# Precharge.net
KiCad netlist of a schematic drawn in Altium Designer
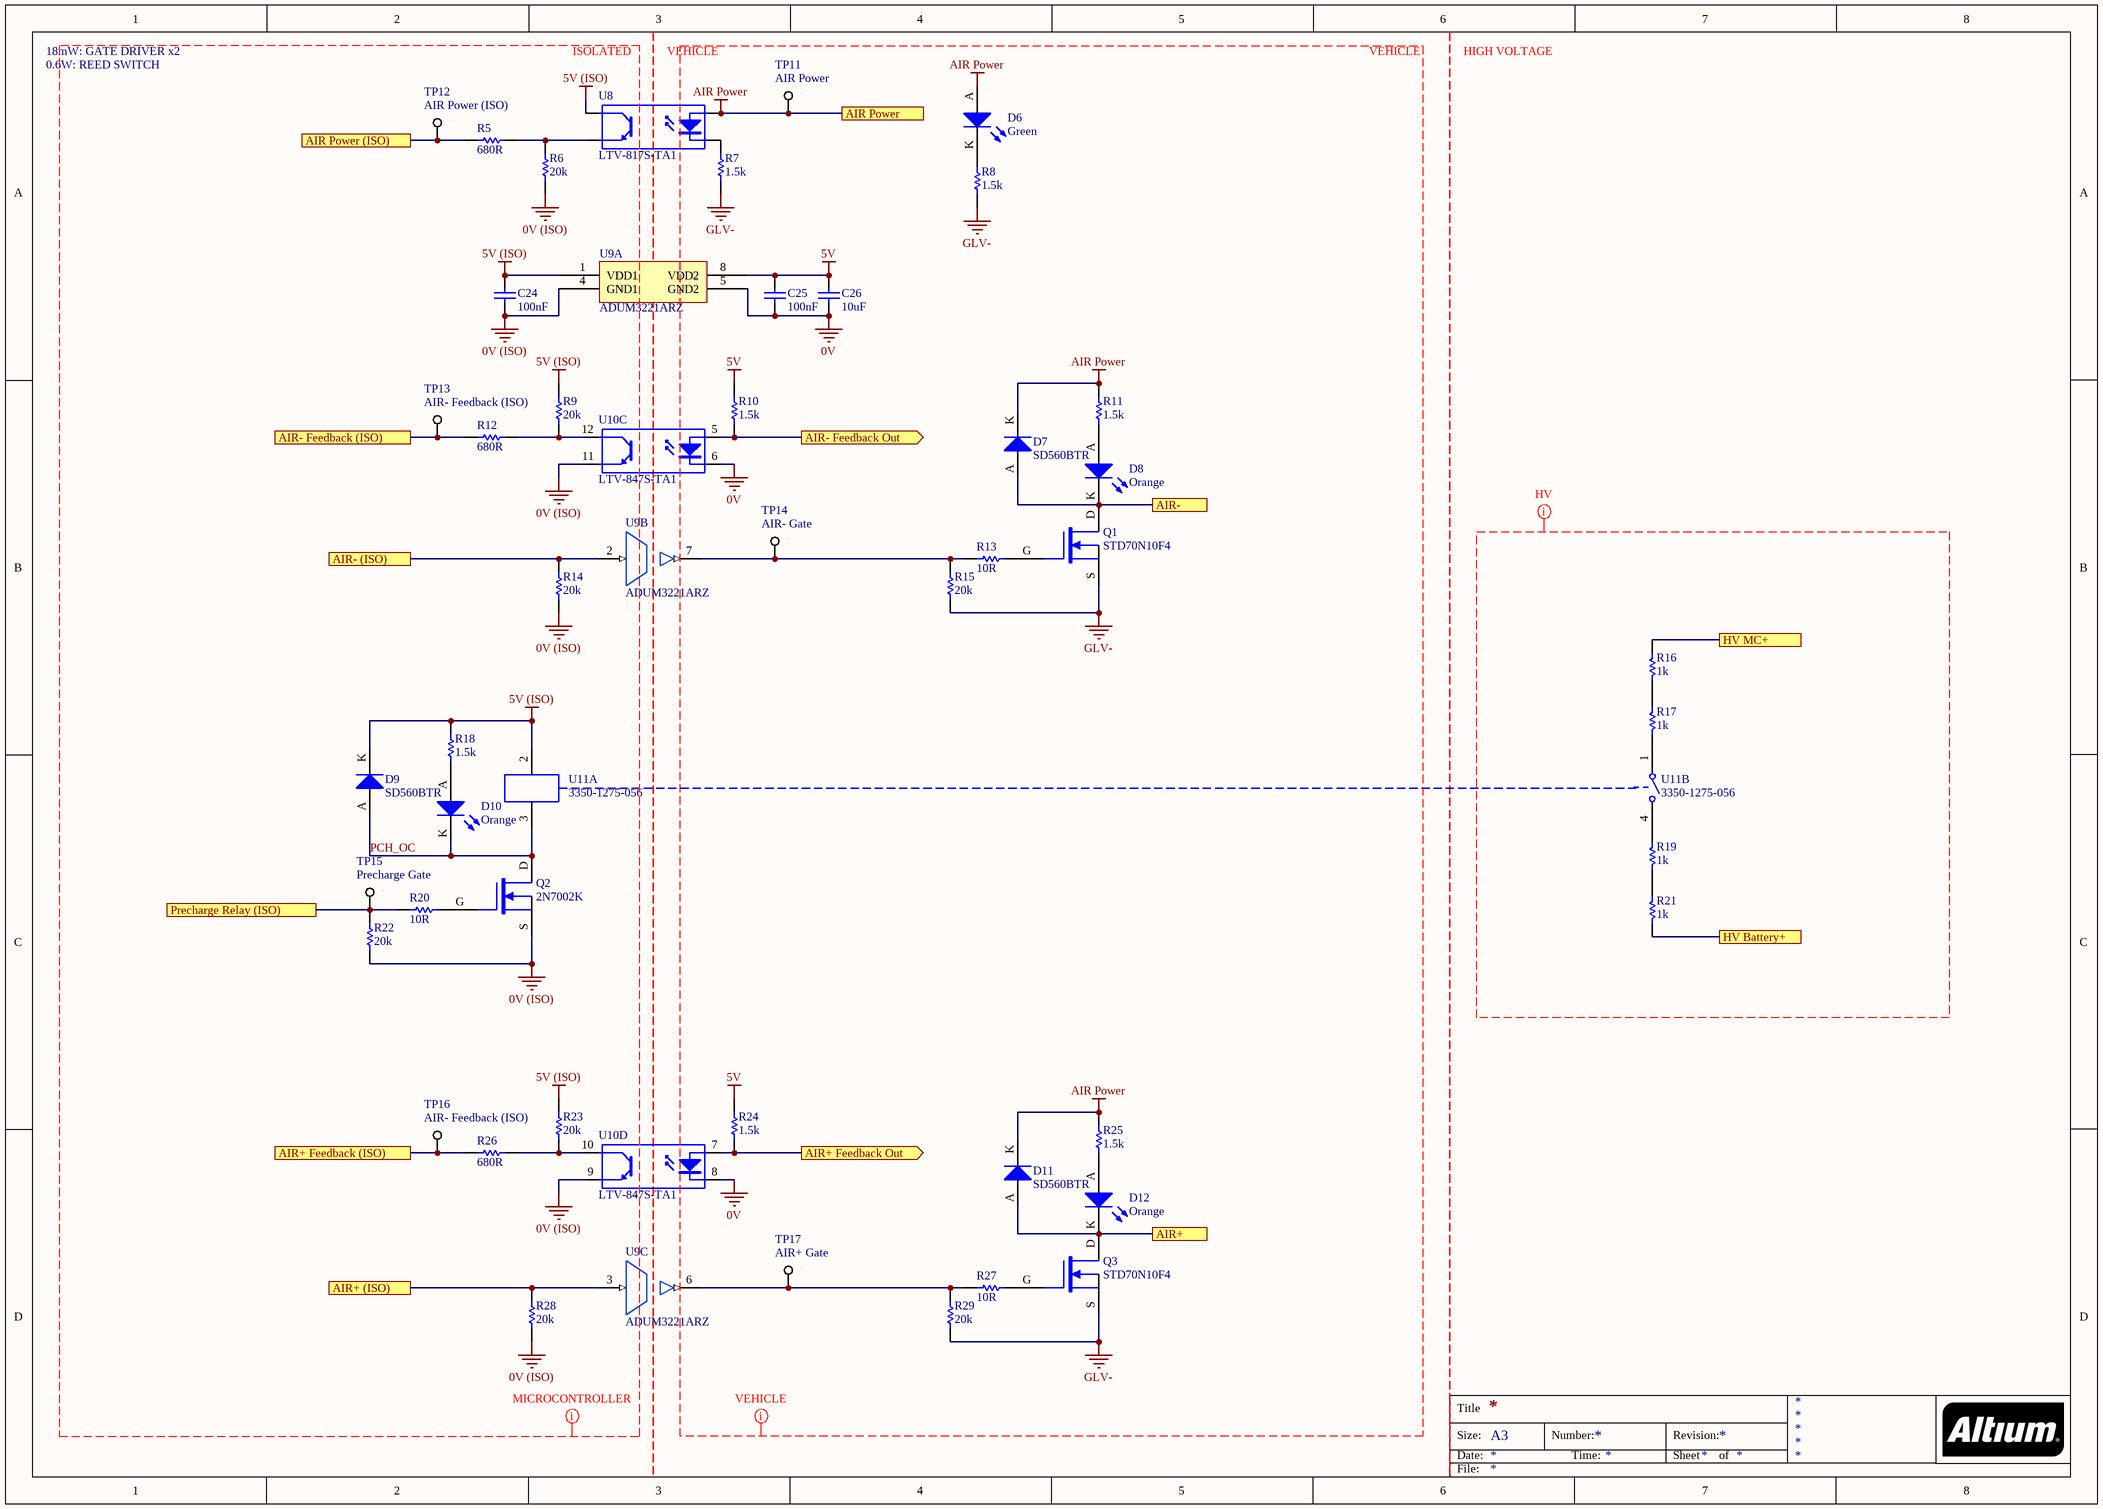
[diagram p0: Precharge.SchDoc]

(export (version "E")
  (design (tool "Eeschema 10.0.6"))
  (components
    (comp (ref "C24")
      (value "100nF")
      (footprint "0805")
      (fields
        (field (name "PART NUMBER") "GCM21BR71H104KA37L")
        (field (name "TOLERANCE") "±10%")
        (field (name "MANUFACTURER") "muRata")
      )
      (libsource (lib "ts_20-standard-library") (part "Capacitor"))
    )
    (comp (ref "C25")
      (value "100nF")
      (footprint "0805")
      (fields
        (field (name "PART NUMBER") "GCM21BR71H104KA37L")
        (field (name "TOLERANCE") "±10%")
        (field (name "MANUFACTURER") "muRata")
      )
      (libsource (lib "ts_20-standard-library") (part "Capacitor"))
    )
    (comp (ref "C26")
      (value "10uF")
      (footprint "0805")
      (fields
        (field (name "PART NUMBER") "GRM21BR6YA106KE43L")
        (field (name "TOLERANCE") "10%")
        (field (name "MANUFACTURER") "muRata")
      )
      (libsource (lib "ts_20-standard-library") (part "Capacitor"))
    )
    (comp (ref "D6")
      (value "Green")
      (footprint "0805 LED")
      (description "Green LED Indication - Discrete 1.75V 0805 (2012 Metric)")
      (fields (field (name "PART NUMBER") "SML-210FTT86") (field (name "MANUFACTURER") "ROHM Semiconductor"))
      (libsource (lib "ts_20-standard-library") (part "LED"))
    )
    (comp (ref "D7")
      (value "SD560BTR")
      (footprint "SMB Diode")
      (description "1.2V_F 600V 5A SMB")
      (fields
        (field (name "MANUFACTURER") "SMC Diode Solutions")
        (field (name "DIGIKEY PART NUMBER") "1655-1530-2-ND")
      )
      (libsource (lib "ts_20-standard-library") (part "Diode"))
    )
    (comp (ref "D8")
      (value "Orange")
      (footprint "0805 LED")
      (description "Orange LED Indication - Discrete 1.75V 0805 (2012 Metric)")
      (fields (field (name "PART NUMBER") "SML-211DTT86") (field (name "MANUFACTURER") "ROHM Semiconductor"))
      (libsource (lib "ts_20-standard-library") (part "LED"))
    )
    (comp (ref "D9")
      (value "SD560BTR")
      (footprint "SMB Diode")
      (description "1.2V_F 600V 5A SMB")
      (fields
        (field (name "MANUFACTURER") "SMC Diode Solutions")
        (field (name "DIGIKEY PART NUMBER") "1655-1530-2-ND")
      )
      (libsource (lib "ts_20-standard-library") (part "Diode"))
    )
    (comp (ref "D10")
      (value "Orange")
      (footprint "0805 LED")
      (description "Orange LED Indication - Discrete 1.75V 0805 (2012 Metric)")
      (fields (field (name "PART NUMBER") "SML-211DTT86") (field (name "MANUFACTURER") "ROHM Semiconductor"))
      (libsource (lib "ts_20-standard-library") (part "LED"))
    )
    (comp (ref "D11")
      (value "SD560BTR")
      (footprint "SMB Diode")
      (description "1.2V_F 600V 5A SMB")
      (fields
        (field (name "MANUFACTURER") "SMC Diode Solutions")
        (field (name "DIGIKEY PART NUMBER") "1655-1530-2-ND")
      )
      (libsource (lib "ts_20-standard-library") (part "Diode"))
    )
    (comp (ref "D12")
      (value "Orange")
      (footprint "0805 LED")
      (description "Orange LED Indication - Discrete 1.75V 0805 (2012 Metric)")
      (fields (field (name "PART NUMBER") "SML-211DTT86") (field (name "MANUFACTURER") "ROHM Semiconductor"))
      (libsource (lib "ts_20-standard-library") (part "LED"))
    )
    (comp (ref "Q1")
      (value "STD70N10F4")
      (footprint "STM TO-252 MOSFET")
      (description "N-Channel 100V 60A (Tc) 125W (Tc) Surface Mount DPAK")
      (fields
        (field (name "MANUFACTURER") "STMicroelectronics")
        (field (name "DIGIKEY PART NUMBER") "497-8806-2-ND")
        (field (name "PUBLISHER") "Altium Limited")
      )
      (libsource (lib "ts_20-standard-library") (part "MOSFET-N"))
    )
    (comp (ref "Q2")
      (value "2N7002K")
      (footprint "ON SOT-23 MOSFET")
      (description "60V 380mA, NFET MOSTFET (Small Signal)")
      (fields
        (field (name "MANUFACTURER") "ON Semiconductor")
        (field (name "DIGIKEY PART NUMBER") "2N7002KCT-ND")
        (field (name "PUBLISHER") "Altium Limited")
      )
      (libsource (lib "ts_20-standard-library") (part "MOSFET-N"))
    )
    (comp (ref "Q3")
      (value "STD70N10F4")
      (footprint "STM TO-252 MOSFET")
      (description "N-Channel 100V 60A (Tc) 125W (Tc) Surface Mount DPAK")
      (fields
        (field (name "MANUFACTURER") "STMicroelectronics")
        (field (name "DIGIKEY PART NUMBER") "497-8806-2-ND")
        (field (name "PUBLISHER") "Altium Limited")
      )
      (libsource (lib "ts_20-standard-library") (part "MOSFET-N"))
    )
    (comp (ref "R5")
      (value "680R")
      (footprint "0805")
      (fields
        (field (name "PART NUMBER") "RC0805FR07680RL")
        (field (name "MANUFACTURER") "YAGEO")
        (field (name "TOLERANCE") "0.01")
      )
      (libsource (lib "ts_20-standard-library") (part "Resistor"))
    )
    (comp (ref "R6")
      (value "20k")
      (footprint "0805")
      (fields
        (field (name "PART NUMBER") "RC0805FR0720KL")
        (field (name "MANUFACTURER") "YAGEO")
        (field (name "TOLERANCE") "0.01")
      )
      (libsource (lib "ts_20-standard-library") (part "Resistor"))
    )
    (comp (ref "R7")
      (value "1.5k")
      (footprint "0805")
      (fields
        (field (name "PART NUMBER") "RC0805FR071K5L")
        (field (name "MANUFACTURER") "YAGEO")
        (field (name "TOLERANCE") "0.01")
      )
      (libsource (lib "ts_20-standard-library") (part "Resistor"))
    )
    (comp (ref "R8")
      (value "1.5k")
      (footprint "0805")
      (fields
        (field (name "PART NUMBER") "RC0805FR071K5L")
        (field (name "MANUFACTURER") "YAGEO")
        (field (name "TOLERANCE") "0.01")
      )
      (libsource (lib "ts_20-standard-library") (part "Resistor"))
    )
    (comp (ref "R9")
      (value "20k")
      (footprint "0805")
      (fields
        (field (name "PART NUMBER") "RC0805FR0720KL")
        (field (name "MANUFACTURER") "YAGEO")
        (field (name "TOLERANCE") "0.01")
      )
      (libsource (lib "ts_20-standard-library") (part "Resistor"))
    )
    (comp (ref "R10")
      (value "1.5k")
      (footprint "0805")
      (fields
        (field (name "PART NUMBER") "RC0805FR071K5L")
        (field (name "MANUFACTURER") "YAGEO")
        (field (name "TOLERANCE") "0.01")
      )
      (libsource (lib "ts_20-standard-library") (part "Resistor"))
    )
    (comp (ref "R11")
      (value "1.5k")
      (footprint "0805")
      (fields
        (field (name "PART NUMBER") "RC0805FR071K5L")
        (field (name "MANUFACTURER") "YAGEO")
        (field (name "TOLERANCE") "0.01")
      )
      (libsource (lib "ts_20-standard-library") (part "Resistor"))
    )
    (comp (ref "R12")
      (value "680R")
      (footprint "0805")
      (fields
        (field (name "PART NUMBER") "RC0805FR07680RL")
        (field (name "MANUFACTURER") "YAGEO")
        (field (name "TOLERANCE") "0.01")
      )
      (libsource (lib "ts_20-standard-library") (part "Resistor"))
    )
    (comp (ref "R13")
      (value "10R")
      (footprint "0805")
      (fields
        (field (name "PART NUMBER") "RC0805FR0710RL")
        (field (name "MANUFACTURER") "YAGEO")
        (field (name "TOLERANCE") "0.01")
      )
      (libsource (lib "ts_20-standard-library") (part "Resistor"))
    )
    (comp (ref "R14")
      (value "20k")
      (footprint "0805")
      (fields
        (field (name "PART NUMBER") "RC0805FR0720KL")
        (field (name "MANUFACTURER") "YAGEO")
        (field (name "TOLERANCE") "0.01")
      )
      (libsource (lib "ts_20-standard-library") (part "Resistor"))
    )
    (comp (ref "R15")
      (value "20k")
      (footprint "0805")
      (fields
        (field (name "PART NUMBER") "RC0805FR0720KL")
        (field (name "MANUFACTURER") "YAGEO")
        (field (name "TOLERANCE") "0.01")
      )
      (libsource (lib "ts_20-standard-library") (part "Resistor"))
    )
    (comp (ref "R16")
      (value "1k")
      (footprint "B TO-263")
      (fields
        (field (name "PART NUMBER") "PWR263S-35-1001J")
        (field (name "MANUFACTURER") "Bournes Inc")
        (field (name "TOLERANCE") "0.05")
      )
      (libsource (lib "ts_20-standard-library") (part "Resistor"))
    )
    (comp (ref "R17")
      (value "1k")
      (footprint "B TO-263")
      (fields
        (field (name "PART NUMBER") "PWR263S-35-1001J")
        (field (name "MANUFACTURER") "Bournes Inc")
        (field (name "TOLERANCE") "0.05")
      )
      (libsource (lib "ts_20-standard-library") (part "Resistor"))
    )
    (comp (ref "R18")
      (value "1.5k")
      (footprint "0805")
      (fields
        (field (name "PART NUMBER") "RC0805FR071K5L")
        (field (name "MANUFACTURER") "YAGEO")
        (field (name "TOLERANCE") "0.01")
      )
      (libsource (lib "ts_20-standard-library") (part "Resistor"))
    )
    (comp (ref "R19")
      (value "1k")
      (footprint "B TO-263")
      (fields
        (field (name "PART NUMBER") "PWR263S-35-1001J")
        (field (name "MANUFACTURER") "Bournes Inc")
        (field (name "TOLERANCE") "0.05")
      )
      (libsource (lib "ts_20-standard-library") (part "Resistor"))
    )
    (comp (ref "R20")
      (value "10R")
      (footprint "0805")
      (fields
        (field (name "PART NUMBER") "RC0805FR0710RL")
        (field (name "MANUFACTURER") "YAGEO")
        (field (name "TOLERANCE") "0.01")
      )
      (libsource (lib "ts_20-standard-library") (part "Resistor"))
    )
    (comp (ref "R21")
      (value "1k")
      (footprint "B TO-263")
      (fields
        (field (name "PART NUMBER") "PWR263S-35-1001J")
        (field (name "MANUFACTURER") "Bournes Inc")
        (field (name "TOLERANCE") "0.05")
      )
      (libsource (lib "ts_20-standard-library") (part "Resistor"))
    )
    (comp (ref "R22")
      (value "20k")
      (footprint "0805")
      (fields
        (field (name "PART NUMBER") "RC0805FR0720KL")
        (field (name "MANUFACTURER") "YAGEO")
        (field (name "TOLERANCE") "0.01")
      )
      (libsource (lib "ts_20-standard-library") (part "Resistor"))
    )
    (comp (ref "R23")
      (value "20k")
      (footprint "0805")
      (fields
        (field (name "PART NUMBER") "RC0805FR0720KL")
        (field (name "MANUFACTURER") "YAGEO")
        (field (name "TOLERANCE") "0.01")
      )
      (libsource (lib "ts_20-standard-library") (part "Resistor"))
    )
    (comp (ref "R24")
      (value "1.5k")
      (footprint "0805")
      (fields
        (field (name "PART NUMBER") "RC0805FR071K5L")
        (field (name "MANUFACTURER") "YAGEO")
        (field (name "TOLERANCE") "0.01")
      )
      (libsource (lib "ts_20-standard-library") (part "Resistor"))
    )
    (comp (ref "R25")
      (value "1.5k")
      (footprint "0805")
      (fields
        (field (name "PART NUMBER") "RC0805FR071K5L")
        (field (name "MANUFACTURER") "YAGEO")
        (field (name "TOLERANCE") "0.01")
      )
      (libsource (lib "ts_20-standard-library") (part "Resistor"))
    )
    (comp (ref "R26")
      (value "680R")
      (footprint "0805")
      (fields
        (field (name "PART NUMBER") "RC0805FR07680RL")
        (field (name "MANUFACTURER") "YAGEO")
        (field (name "TOLERANCE") "0.01")
      )
      (libsource (lib "ts_20-standard-library") (part "Resistor"))
    )
    (comp (ref "R27")
      (value "10R")
      (footprint "0805")
      (fields
        (field (name "PART NUMBER") "RC0805FR0710RL")
        (field (name "MANUFACTURER") "YAGEO")
        (field (name "TOLERANCE") "0.01")
      )
      (libsource (lib "ts_20-standard-library") (part "Resistor"))
    )
    (comp (ref "R28")
      (value "20k")
      (footprint "0805")
      (fields
        (field (name "PART NUMBER") "RC0805FR0720KL")
        (field (name "MANUFACTURER") "YAGEO")
        (field (name "TOLERANCE") "0.01")
      )
      (libsource (lib "ts_20-standard-library") (part "Resistor"))
    )
    (comp (ref "R29")
      (value "20k")
      (footprint "0805")
      (fields
        (field (name "PART NUMBER") "RC0805FR0720KL")
        (field (name "MANUFACTURER") "YAGEO")
        (field (name "TOLERANCE") "0.01")
      )
      (libsource (lib "ts_20-standard-library") (part "Resistor"))
    )
    (comp (ref "TP11")
      (value "AIR Power")
      (footprint "SMD Test Point 1mm")
      (fields (field (name "PART NUMBER") "SMD Test Point Small") (field (name "CONTACT") "NA"))
      (libsource (lib "ts_20-standard-connectors") (part "Test Point Small"))
    )
    (comp (ref "TP12")
      (value "AIR Power (ISO)")
      (footprint "SMD Test Point 1mm")
      (fields (field (name "PART NUMBER") "SMD Test Point Small") (field (name "CONTACT") "NA"))
      (libsource (lib "ts_20-standard-connectors") (part "Test Point Small"))
    )
    (comp (ref "TP13")
      (value "AIR- Feedback (ISO)")
      (footprint "SMD Test Point 1mm")
      (fields (field (name "PART NUMBER") "SMD Test Point Small") (field (name "CONTACT") "NA"))
      (libsource (lib "ts_20-standard-connectors") (part "Test Point Small"))
    )
    (comp (ref "TP14")
      (value "AIR- Gate")
      (footprint "SMD Test Point 1mm")
      (fields (field (name "PART NUMBER") "SMD Test Point Small") (field (name "CONTACT") "NA"))
      (libsource (lib "ts_20-standard-connectors") (part "Test Point Small"))
    )
    (comp (ref "TP15")
      (value "Precharge Gate")
      (footprint "SMD Test Point 1mm")
      (fields (field (name "PART NUMBER") "SMD Test Point Small") (field (name "CONTACT") "NA"))
      (libsource (lib "ts_20-standard-connectors") (part "Test Point Small"))
    )
    (comp (ref "TP16")
      (value "AIR- Feedback (ISO)")
      (footprint "SMD Test Point 1mm")
      (fields (field (name "PART NUMBER") "SMD Test Point Small") (field (name "CONTACT") "NA"))
      (libsource (lib "ts_20-standard-connectors") (part "Test Point Small"))
    )
    (comp (ref "TP17")
      (value "AIR+ Gate")
      (footprint "SMD Test Point 1mm")
      (fields (field (name "PART NUMBER") "SMD Test Point Small") (field (name "CONTACT") "NA"))
      (libsource (lib "ts_20-standard-connectors") (part "Test Point Small"))
    )
    (comp (ref "U8")
      (value "LTV-817S-TA1")
      (footprint "ON 4-SMD")
      (description "35V 50ma Optocoupler (VF=1.2V)")
      (fields
        (field (name "MANUFACTURER") "Lite-On Inc")
        (field (name "DIGIKEY PART NUMBER") "160-1893-2-ND")
      )
      (libsource (lib "ts_20-standard-library") (part "LTV-817S-TA1"))
    )
    (comp (ref "U9")
      (value "ADUM3221ARZ")
      (footprint "AD 8-SOIC")
      (description "4A Gate Driver Magnetic Coupling 2500Vrms 2 Channel 8-SOIC")
      (fields
        (field (name "MANUFACTURER") "Analog Devices")
        (field (name "DIGIKEY PART NUMBER") "ADUM3221ARZ-ND")
      )
      (libsource (lib "ts_20-standard-library") (part "ADuM3221"))
    )
    (comp (ref "U10")
      (value "LTV-847S-TA1")
      (footprint "ON 16-SMD")
      (description "Optoisolator Transistor Output 5000Vrms 4 Channel 16-SMD")
      (fields
        (field (name "MANUFACTURER") "Lite-On Inc")
        (field (name "DIGIKEY PART NUMBER") "160-1371-5-ND")
      )
      (libsource (lib "ts_20-standard-library") (part "LTV-847S-TA1"))
    )
    (comp (ref "U11")
      (value "3350-1275-056")
      (footprint "CI SPST")
      (description "RELAY REED HV SPST 200W 3A 5V (NO)")
      (fields
        (field (name "MANUFACTURER") "Comus International")
        (field (name "DIGIKEY PART NUMBER") "1835-1036-ND")
      )
      (libsource (lib "ts_20-standard-library") (part "3350-1275-056"))
    )
  )
  (nets
    (net (code "1") (name "/AIR Power (ISO)") (class "Default")
      (node (ref "R5") (pin "1") (pinfunction "1_1") (pintype "passive"))
      (node (ref "TP12") (pin "1") (pinfunction "1_1") (pintype "passive"))
    )
    (net (code "2") (name "/AIR+") (class "Default")
      (node (ref "D11") (pin "A") (pinfunction "A_A") (pintype "passive"))
      (node (ref "D12") (pin "K") (pinfunction "K_K") (pintype "passive"))
      (node (ref "Q3") (pin "D") (pinfunction "D_D") (pintype "passive"))
    )
    (net (code "3") (name "/AIR+ (ISO)") (class "Default")
      (node (ref "R28") (pin "2") (pinfunction "2_2") (pintype "passive"))
      (node (ref "U9") (pin "3") (pinfunction "VIA_3") (pintype "input"))
    )
    (net (code "4") (name "/AIR+ Feedback (ISO)") (class "Default")
      (node (ref "R26") (pin "1") (pinfunction "1_1") (pintype "passive"))
      (node (ref "TP16") (pin "1") (pinfunction "1_1") (pintype "passive"))
    )
    (net (code "5") (name "/AIR+ Feedback Out") (class "Default")
      (node (ref "R24") (pin "1") (pinfunction "1_1") (pintype "passive"))
      (node (ref "U10") (pin "7") (pinfunction "A_7") (pintype "passive"))
    )
    (net (code "6") (name "/AIR-") (class "Default")
      (node (ref "D7") (pin "A") (pinfunction "A_A") (pintype "passive"))
      (node (ref "D8") (pin "K") (pinfunction "K_K") (pintype "passive"))
      (node (ref "Q1") (pin "D") (pinfunction "D_D") (pintype "passive"))
    )
    (net (code "7") (name "/AIR- (ISO)") (class "Default")
      (node (ref "R14") (pin "2") (pinfunction "2_2") (pintype "passive"))
      (node (ref "U9") (pin "2") (pinfunction "VIA_2") (pintype "input"))
    )
    (net (code "8") (name "/AIR- Feedback (ISO)") (class "Default")
      (node (ref "R12") (pin "1") (pinfunction "1_1") (pintype "passive"))
      (node (ref "TP13") (pin "1") (pinfunction "1_1") (pintype "passive"))
    )
    (net (code "9") (name "/AIR- Feedback Out") (class "Default")
      (node (ref "R10") (pin "1") (pinfunction "1_1") (pintype "passive"))
      (node (ref "U10") (pin "5") (pinfunction "A_5") (pintype "passive"))
    )
    (net (code "10") (name "/HV Battery+") (class "Default")
      (node (ref "R21") (pin "1") (pinfunction "1_1") (pintype "passive"))
    )
    (net (code "11") (name "/HV MC+") (class "Default")
      (node (ref "R16") (pin "2") (pinfunction "2_2") (pintype "passive"))
    )
    (net (code "12") (name "/PCH_OC") (class "Default")
      (node (ref "D10") (pin "K") (pinfunction "K_K") (pintype "passive"))
      (node (ref "D9") (pin "A") (pinfunction "A_A") (pintype "passive"))
      (node (ref "Q2") (pin "D") (pinfunction "D_D") (pintype "passive"))
      (node (ref "U11") (pin "3") (pinfunction "3_3") (pintype "passive"))
    )
    (net (code "13") (name "/Precharge Relay (ISO)") (class "Default")
      (node (ref "R20") (pin "1") (pinfunction "1_1") (pintype "passive"))
      (node (ref "R22") (pin "2") (pinfunction "2_2") (pintype "passive"))
      (node (ref "TP15") (pin "1") (pinfunction "1_1") (pintype "passive"))
    )
    (net (code "14") (name "0V") (class "Default")
      (node (ref "C25") (pin "1") (pinfunction "1_1") (pintype "passive"))
      (node (ref "C26") (pin "1") (pinfunction "1_1") (pintype "passive"))
      (node (ref "U10") (pin "6") (pinfunction "K_6") (pintype "passive"))
      (node (ref "U10") (pin "8") (pinfunction "K_8") (pintype "passive"))
      (node (ref "U9") (pin "5") (pinfunction "GND2_5") (pintype "passive"))
    )
    (net (code "15") (name "0V (ISO)") (class "Default")
      (node (ref "C24") (pin "1") (pinfunction "1_1") (pintype "passive"))
      (node (ref "Q2") (pin "S") (pinfunction "S_S") (pintype "passive"))
      (node (ref "R14") (pin "1") (pinfunction "1_1") (pintype "passive"))
      (node (ref "R22") (pin "1") (pinfunction "1_1") (pintype "passive"))
      (node (ref "R28") (pin "1") (pinfunction "1_1") (pintype "passive"))
      (node (ref "R6") (pin "1") (pinfunction "1_1") (pintype "passive"))
      (node (ref "U10") (pin "11") (pinfunction "E_11") (pintype "passive"))
      (node (ref "U10") (pin "9") (pinfunction "E_9") (pintype "passive"))
      (node (ref "U9") (pin "4") (pinfunction "GND1_4") (pintype "passive"))
    )
    (net (code "16") (name "5V") (class "Default")
      (node (ref "C25") (pin "2") (pinfunction "2_2") (pintype "passive"))
      (node (ref "C26") (pin "2") (pinfunction "2_2") (pintype "passive"))
      (node (ref "R10") (pin "2") (pinfunction "2_2") (pintype "passive"))
      (node (ref "R24") (pin "2") (pinfunction "2_2") (pintype "passive"))
      (node (ref "U9") (pin "8") (pinfunction "VDD2_8") (pintype "passive"))
    )
    (net (code "17") (name "5V (ISO)") (class "Default")
      (node (ref "C24") (pin "2") (pinfunction "2_2") (pintype "passive"))
      (node (ref "D9") (pin "K") (pinfunction "K_K") (pintype "passive"))
      (node (ref "R18") (pin "2") (pinfunction "2_2") (pintype "passive"))
      (node (ref "R23") (pin "2") (pinfunction "2_2") (pintype "passive"))
      (node (ref "R9") (pin "2") (pinfunction "2_2") (pintype "passive"))
      (node (ref "U11") (pin "2") (pinfunction "2_2") (pintype "passive"))
      (node (ref "U8") (pin "4") (pinfunction "C_4") (pintype "passive"))
      (node (ref "U9") (pin "1") (pinfunction "VDD1_1") (pintype "passive"))
    )
    (net (code "18") (name "AIR Power") (class "Default")
      (node (ref "D11") (pin "K") (pinfunction "K_K") (pintype "passive"))
      (node (ref "D6") (pin "A") (pinfunction "A_A") (pintype "passive"))
      (node (ref "D7") (pin "K") (pinfunction "K_K") (pintype "passive"))
      (node (ref "R11") (pin "2") (pinfunction "2_2") (pintype "passive"))
      (node (ref "R25") (pin "2") (pinfunction "2_2") (pintype "passive"))
      (node (ref "TP11") (pin "1") (pinfunction "1_1") (pintype "passive"))
      (node (ref "U8") (pin "1") (pinfunction "A_1") (pintype "passive"))
    )
    (net (code "19") (name "GLV-") (class "Default")
      (node (ref "Q1") (pin "S") (pinfunction "S_S") (pintype "passive"))
      (node (ref "Q3") (pin "S") (pinfunction "S_S") (pintype "passive"))
      (node (ref "R15") (pin "1") (pinfunction "1_1") (pintype "passive"))
      (node (ref "R29") (pin "1") (pinfunction "1_1") (pintype "passive"))
      (node (ref "R7") (pin "2") (pinfunction "2_2") (pintype "passive"))
      (node (ref "R8") (pin "2") (pinfunction "2_2") (pintype "passive"))
    )
    (net (code "20") (name "Net-(D6-PadK)") (class "Default")
      (node (ref "D6") (pin "K") (pinfunction "K_K") (pintype "passive"))
      (node (ref "R8") (pin "1") (pinfunction "1_1") (pintype "passive"))
    )
    (net (code "21") (name "Net-(D8-PadA)") (class "Default")
      (node (ref "D8") (pin "A") (pinfunction "A_A") (pintype "passive"))
      (node (ref "R11") (pin "1") (pinfunction "1_1") (pintype "passive"))
    )
    (net (code "22") (name "Net-(D10-PadA)") (class "Default")
      (node (ref "D10") (pin "A") (pinfunction "A_A") (pintype "passive"))
      (node (ref "R18") (pin "1") (pinfunction "1_1") (pintype "passive"))
    )
    (net (code "23") (name "Net-(D12-PadA)") (class "Default")
      (node (ref "D12") (pin "A") (pinfunction "A_A") (pintype "passive"))
      (node (ref "R25") (pin "1") (pinfunction "1_1") (pintype "passive"))
    )
    (net (code "24") (name "Net-(Q1-PadG)") (class "Default")
      (node (ref "Q1") (pin "G") (pinfunction "G_G") (pintype "passive"))
      (node (ref "R13") (pin "2") (pinfunction "2_2") (pintype "passive"))
    )
    (net (code "25") (name "Net-(Q2-PadG)") (class "Default")
      (node (ref "Q2") (pin "G") (pinfunction "G_G") (pintype "passive"))
      (node (ref "R20") (pin "2") (pinfunction "2_2") (pintype "passive"))
    )
    (net (code "26") (name "Net-(Q3-PadG)") (class "Default")
      (node (ref "Q3") (pin "G") (pinfunction "G_G") (pintype "passive"))
      (node (ref "R27") (pin "2") (pinfunction "2_2") (pintype "passive"))
    )
    (net (code "27") (name "Net-(R16-Pad1)") (class "Default")
      (node (ref "R16") (pin "1") (pinfunction "1_1") (pintype "passive"))
      (node (ref "R17") (pin "2") (pinfunction "2_2") (pintype "passive"))
    )
    (net (code "28") (name "Net-(R17-Pad1)") (class "Default")
      (node (ref "R17") (pin "1") (pinfunction "1_1") (pintype "passive"))
      (node (ref "U11") (pin "1") (pinfunction "1_1") (pintype "passive"))
    )
    (net (code "29") (name "Net-(R19-Pad1)") (class "Default")
      (node (ref "R19") (pin "1") (pinfunction "1_1") (pintype "passive"))
      (node (ref "R21") (pin "2") (pinfunction "2_2") (pintype "passive"))
    )
    (net (code "30") (name "Net-(R19-Pad2)") (class "Default")
      (node (ref "R19") (pin "2") (pinfunction "2_2") (pintype "passive"))
      (node (ref "U11") (pin "4") (pinfunction "4_4") (pintype "passive"))
    )
    (net (code "31") (name "Net-(U8-E)") (class "Default")
      (node (ref "R5") (pin "2") (pinfunction "2_2") (pintype "passive"))
      (node (ref "R6") (pin "2") (pinfunction "2_2") (pintype "passive"))
      (node (ref "U8") (pin "3") (pinfunction "E_3") (pintype "passive"))
    )
    (net (code "32") (name "Net-(U8-K)") (class "Default")
      (node (ref "R7") (pin "1") (pinfunction "1_1") (pintype "passive"))
      (node (ref "U8") (pin "2") (pinfunction "K_2") (pintype "passive"))
    )
    (net (code "33") (name "Net-(U9B-VOA)") (class "Default")
      (node (ref "R13") (pin "1") (pinfunction "1_1") (pintype "passive"))
      (node (ref "R15") (pin "2") (pinfunction "2_2") (pintype "passive"))
      (node (ref "TP14") (pin "1") (pinfunction "1_1") (pintype "passive"))
      (node (ref "U9") (pin "7") (pinfunction "VOA_7") (pintype "output"))
    )
    (net (code "34") (name "Net-(U9C-VOA)") (class "Default")
      (node (ref "R27") (pin "1") (pinfunction "1_1") (pintype "passive"))
      (node (ref "R29") (pin "2") (pinfunction "2_2") (pintype "passive"))
      (node (ref "TP17") (pin "1") (pinfunction "1_1") (pintype "passive"))
      (node (ref "U9") (pin "6") (pinfunction "VOA_6") (pintype "output"))
    )
    (net (code "35") (name "Net-(U10C-C)") (class "Default")
      (node (ref "R12") (pin "2") (pinfunction "2_2") (pintype "passive"))
      (node (ref "R9") (pin "1") (pinfunction "1_1") (pintype "passive"))
      (node (ref "U10") (pin "12") (pinfunction "C_12") (pintype "passive"))
    )
    (net (code "36") (name "Net-(U10D-C)") (class "Default")
      (node (ref "R23") (pin "1") (pinfunction "1_1") (pintype "passive"))
      (node (ref "R26") (pin "2") (pinfunction "2_2") (pintype "passive"))
      (node (ref "U10") (pin "10") (pinfunction "C_10") (pintype "passive"))
    )
  )
)
